# PCB_3U_ADC.net
KiCad netlist of a schematic drawn in Altium Designer
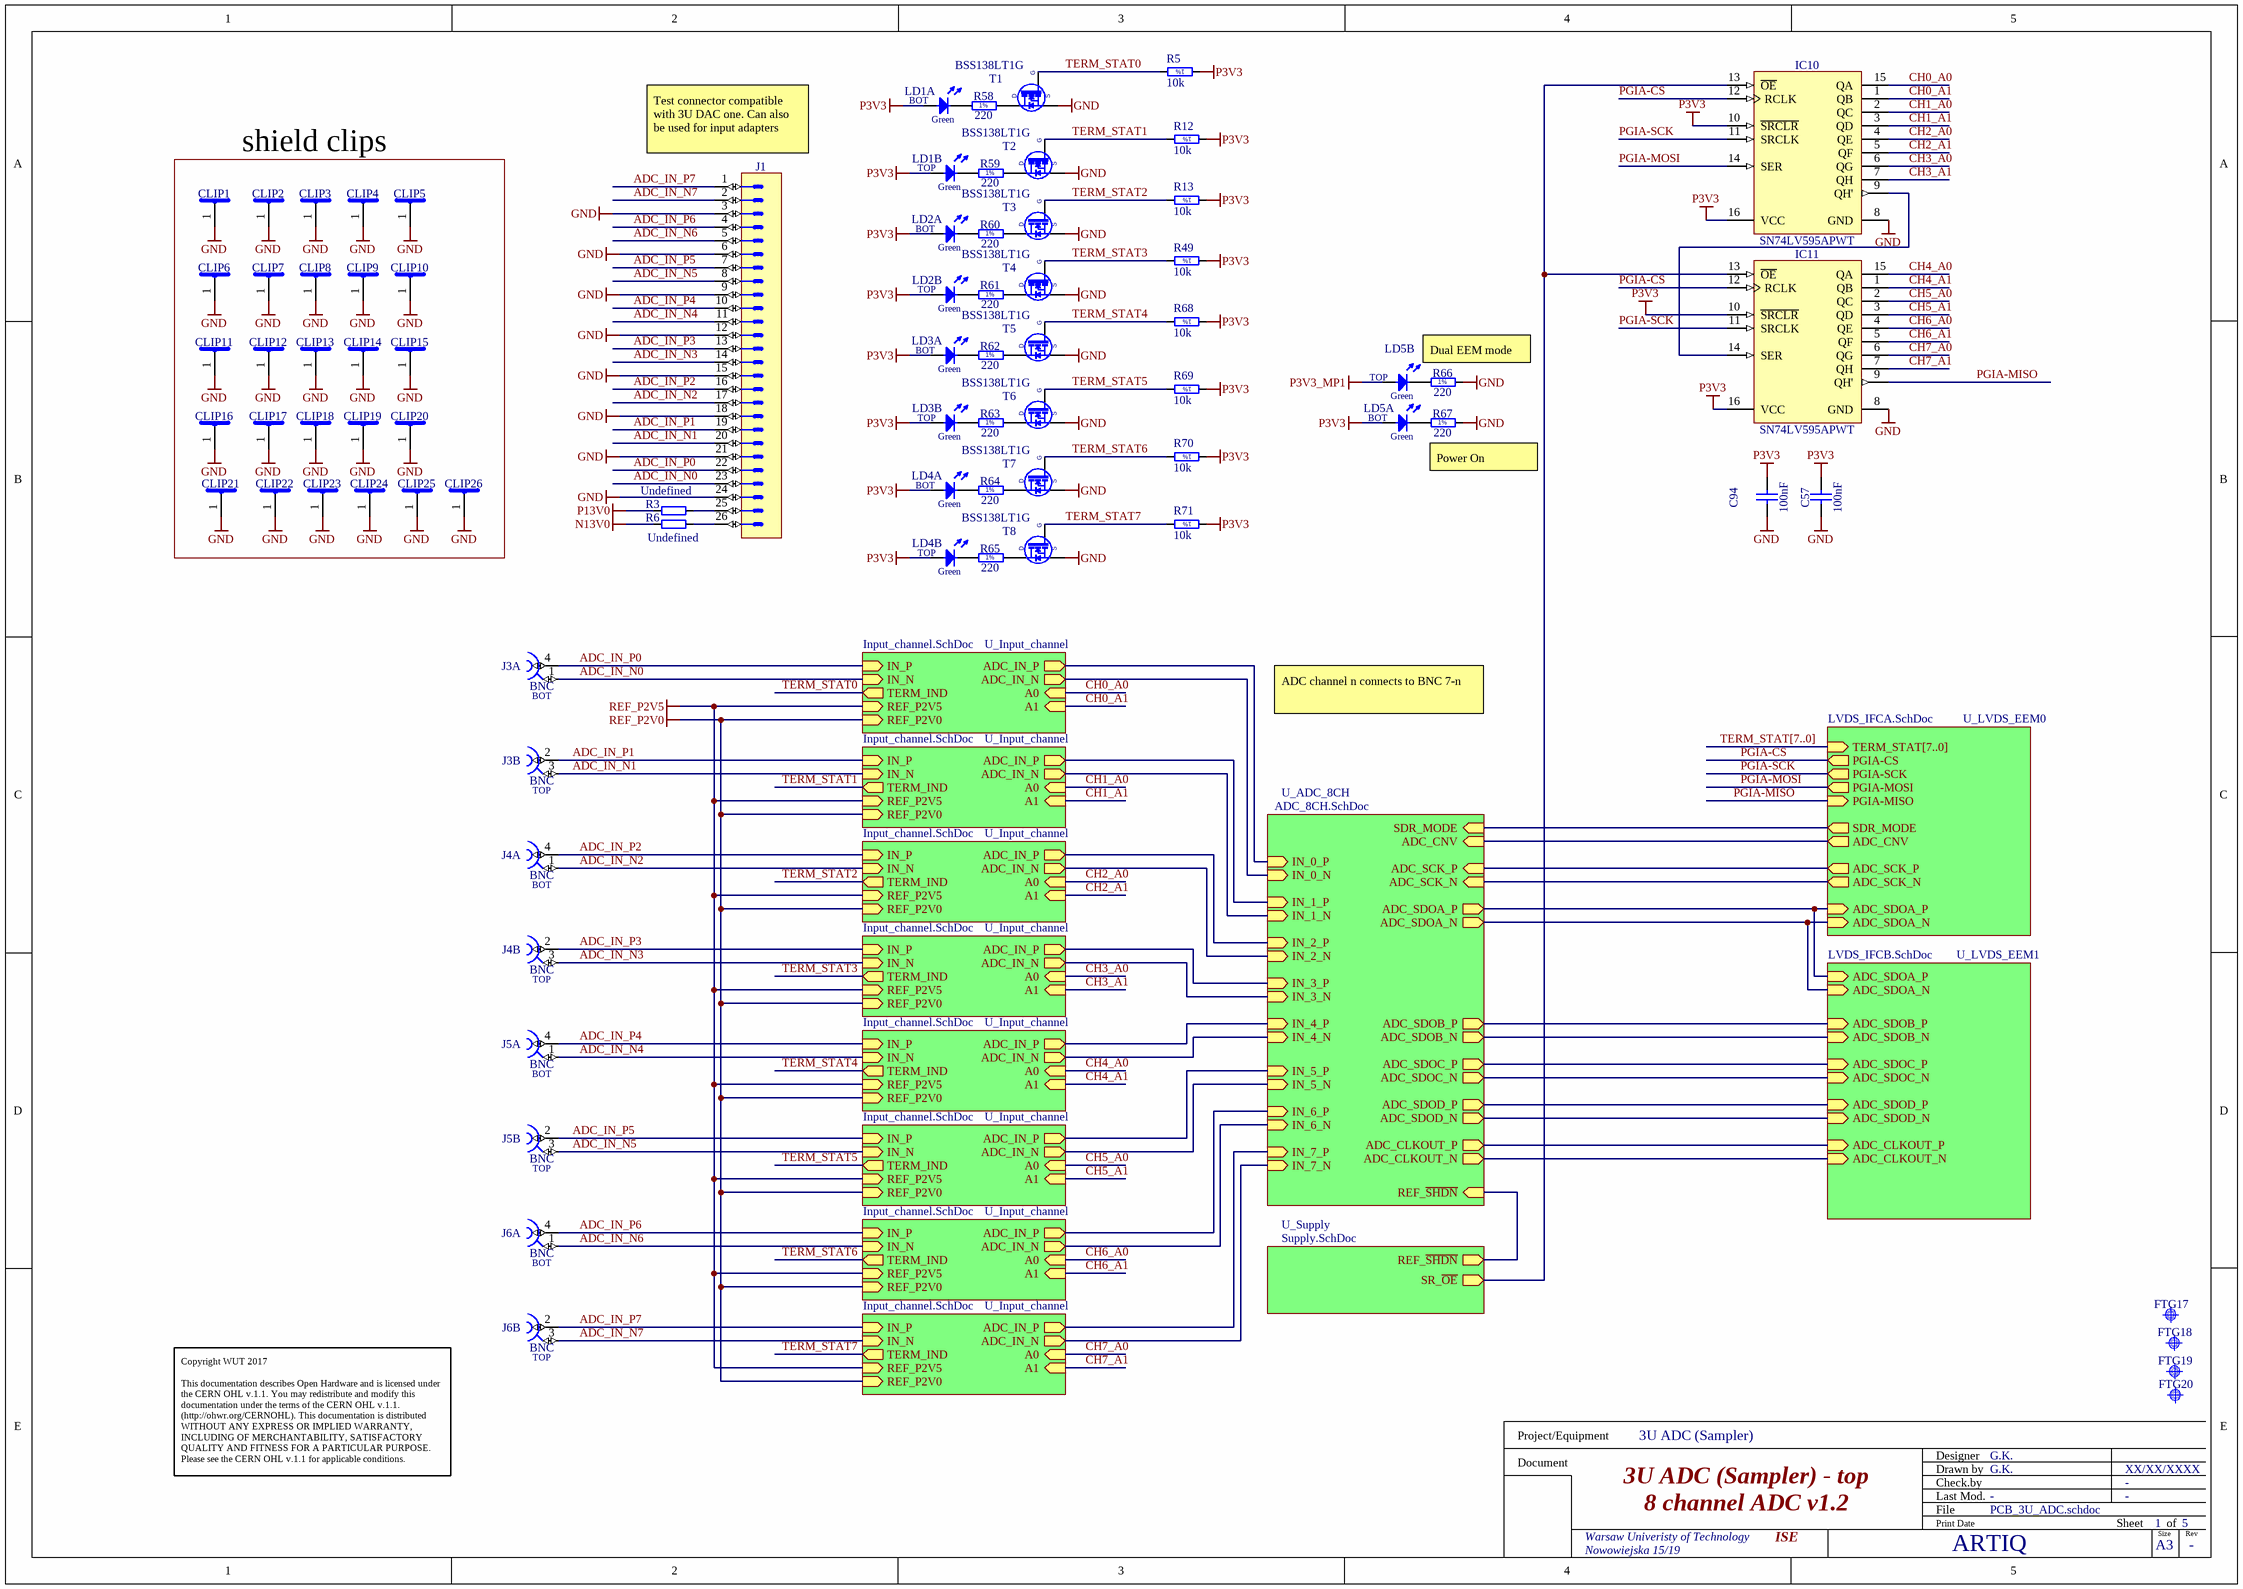
[diagram p0: PCB_3U_ADC.schdoc]

(export (version "E")
  (design (tool "Eeschema 10.0.6"))
  (components
    (comp (ref "C57")
      (value "100nF")
      (footprint "CAPC1608X87N")
      (description "Non-polarised capacitor")
      (fields
        (field (name "PART NUMBER") "CC0603_100NF_50V_10%_X7R")
        (field (name "VOLTAGE") "50V")
        (field (name "AUTHOR") "CERN DEM JLC")
      )
      (libsource (lib "Capacitors") (part "Capacitor - non polarized"))
    )
    (comp (ref "C94")
      (value "100nF")
      (footprint "CAPC1608X87N")
      (description "Non-polarised capacitor")
      (fields
        (field (name "PART NUMBER") "CC0603_100NF_50V_10%_X7R")
        (field (name "VOLTAGE") "50V")
        (field (name "AUTHOR") "CERN DEM JLC")
      )
      (libsource (lib "Capacitors") (part "Capacitor - non polarized"))
    )
    (comp (ref "CLIP1")
      (value "S1411-46R")
      (footprint "CLIP_HOLLAND-SHIELDING_LC")
      (description "Surface Mount Clip for PCB Screening Covers")
      (fields (field (name "MANUFACTURER") "HARWIN") (field (name "AUTHOR") "CERN DEM JLC"))
      (libsource (lib "LIBRARY_SCH") (part "SHIELD_CLIP"))
    )
    (comp (ref "CLIP2")
      (value "S1411-46R")
      (footprint "CLIP_HOLLAND-SHIELDING_LC")
      (description "Surface Mount Clip for PCB Screening Covers")
      (fields (field (name "MANUFACTURER") "HARWIN") (field (name "AUTHOR") "CERN DEM JLC"))
      (libsource (lib "LIBRARY_SCH") (part "SHIELD_CLIP"))
    )
    (comp (ref "CLIP3")
      (value "S1411-46R")
      (footprint "CLIP_HOLLAND-SHIELDING_LC")
      (description "Surface Mount Clip for PCB Screening Covers")
      (fields (field (name "MANUFACTURER") "HARWIN") (field (name "AUTHOR") "CERN DEM JLC"))
      (libsource (lib "LIBRARY_SCH") (part "SHIELD_CLIP"))
    )
    (comp (ref "CLIP4")
      (value "S1411-46R")
      (footprint "CLIP_HOLLAND-SHIELDING_LC")
      (description "Surface Mount Clip for PCB Screening Covers")
      (fields (field (name "MANUFACTURER") "HARWIN") (field (name "AUTHOR") "CERN DEM JLC"))
      (libsource (lib "LIBRARY_SCH") (part "SHIELD_CLIP"))
    )
    (comp (ref "CLIP5")
      (value "S1411-46R")
      (footprint "CLIP_HOLLAND-SHIELDING_LC")
      (description "Surface Mount Clip for PCB Screening Covers")
      (fields (field (name "MANUFACTURER") "HARWIN") (field (name "AUTHOR") "CERN DEM JLC"))
      (libsource (lib "LIBRARY_SCH") (part "SHIELD_CLIP"))
    )
    (comp (ref "CLIP6")
      (value "S1411-46R")
      (footprint "CLIP_HOLLAND-SHIELDING_LC")
      (description "Surface Mount Clip for PCB Screening Covers")
      (fields (field (name "MANUFACTURER") "HARWIN") (field (name "AUTHOR") "CERN DEM JLC"))
      (libsource (lib "LIBRARY_SCH") (part "SHIELD_CLIP"))
    )
    (comp (ref "CLIP7")
      (value "S1411-46R")
      (footprint "CLIP_HOLLAND-SHIELDING_LC")
      (description "Surface Mount Clip for PCB Screening Covers")
      (fields (field (name "MANUFACTURER") "HARWIN") (field (name "AUTHOR") "CERN DEM JLC"))
      (libsource (lib "LIBRARY_SCH") (part "SHIELD_CLIP"))
    )
    (comp (ref "CLIP8")
      (value "S1411-46R")
      (footprint "CLIP_HOLLAND-SHIELDING_LC")
      (description "Surface Mount Clip for PCB Screening Covers")
      (fields (field (name "MANUFACTURER") "HARWIN") (field (name "AUTHOR") "CERN DEM JLC"))
      (libsource (lib "LIBRARY_SCH") (part "SHIELD_CLIP"))
    )
    (comp (ref "CLIP9")
      (value "S1411-46R")
      (footprint "CLIP_HOLLAND-SHIELDING_LC")
      (description "Surface Mount Clip for PCB Screening Covers")
      (fields (field (name "MANUFACTURER") "HARWIN") (field (name "AUTHOR") "CERN DEM JLC"))
      (libsource (lib "LIBRARY_SCH") (part "SHIELD_CLIP"))
    )
    (comp (ref "CLIP10")
      (value "S1411-46R")
      (footprint "CLIP_HOLLAND-SHIELDING_LC")
      (description "Surface Mount Clip for PCB Screening Covers")
      (fields (field (name "MANUFACTURER") "HARWIN") (field (name "AUTHOR") "CERN DEM JLC"))
      (libsource (lib "LIBRARY_SCH") (part "SHIELD_CLIP"))
    )
    (comp (ref "CLIP11")
      (value "S1411-46R")
      (footprint "CLIP_HOLLAND-SHIELDING_LC")
      (description "Surface Mount Clip for PCB Screening Covers")
      (fields (field (name "MANUFACTURER") "HARWIN") (field (name "AUTHOR") "CERN DEM JLC"))
      (libsource (lib "LIBRARY_SCH") (part "SHIELD_CLIP"))
    )
    (comp (ref "CLIP12")
      (value "S1411-46R")
      (footprint "CLIP_HOLLAND-SHIELDING_LC")
      (description "Surface Mount Clip for PCB Screening Covers")
      (fields (field (name "MANUFACTURER") "HARWIN") (field (name "AUTHOR") "CERN DEM JLC"))
      (libsource (lib "LIBRARY_SCH") (part "SHIELD_CLIP"))
    )
    (comp (ref "CLIP13")
      (value "S1411-46R")
      (footprint "CLIP_HOLLAND-SHIELDING_LC")
      (description "Surface Mount Clip for PCB Screening Covers")
      (fields (field (name "MANUFACTURER") "HARWIN") (field (name "AUTHOR") "CERN DEM JLC"))
      (libsource (lib "LIBRARY_SCH") (part "SHIELD_CLIP"))
    )
    (comp (ref "CLIP14")
      (value "S1411-46R")
      (footprint "CLIP_HOLLAND-SHIELDING_LC")
      (description "Surface Mount Clip for PCB Screening Covers")
      (fields (field (name "MANUFACTURER") "HARWIN") (field (name "AUTHOR") "CERN DEM JLC"))
      (libsource (lib "LIBRARY_SCH") (part "SHIELD_CLIP"))
    )
    (comp (ref "CLIP15")
      (value "S1411-46R")
      (footprint "CLIP_HOLLAND-SHIELDING_LC")
      (description "Surface Mount Clip for PCB Screening Covers")
      (fields (field (name "MANUFACTURER") "HARWIN") (field (name "AUTHOR") "CERN DEM JLC"))
      (libsource (lib "LIBRARY_SCH") (part "SHIELD_CLIP"))
    )
    (comp (ref "CLIP16")
      (value "S1411-46R")
      (footprint "CLIP_HOLLAND-SHIELDING_LC")
      (description "Surface Mount Clip for PCB Screening Covers")
      (fields (field (name "MANUFACTURER") "HARWIN") (field (name "AUTHOR") "CERN DEM JLC"))
      (libsource (lib "LIBRARY_SCH") (part "SHIELD_CLIP"))
    )
    (comp (ref "CLIP17")
      (value "S1411-46R")
      (footprint "CLIP_HOLLAND-SHIELDING_LC")
      (description "Surface Mount Clip for PCB Screening Covers")
      (fields (field (name "MANUFACTURER") "HARWIN") (field (name "AUTHOR") "CERN DEM JLC"))
      (libsource (lib "LIBRARY_SCH") (part "SHIELD_CLIP"))
    )
    (comp (ref "CLIP18")
      (value "S1411-46R")
      (footprint "CLIP_HOLLAND-SHIELDING_LC")
      (description "Surface Mount Clip for PCB Screening Covers")
      (fields (field (name "MANUFACTURER") "HARWIN") (field (name "AUTHOR") "CERN DEM JLC"))
      (libsource (lib "LIBRARY_SCH") (part "SHIELD_CLIP"))
    )
    (comp (ref "CLIP19")
      (value "S1411-46R")
      (footprint "CLIP_HOLLAND-SHIELDING_LC")
      (description "Surface Mount Clip for PCB Screening Covers")
      (fields (field (name "MANUFACTURER") "HARWIN") (field (name "AUTHOR") "CERN DEM JLC"))
      (libsource (lib "LIBRARY_SCH") (part "SHIELD_CLIP"))
    )
    (comp (ref "CLIP20")
      (value "S1411-46R")
      (footprint "CLIP_HOLLAND-SHIELDING_LC")
      (description "Surface Mount Clip for PCB Screening Covers")
      (fields (field (name "MANUFACTURER") "HARWIN") (field (name "AUTHOR") "CERN DEM JLC"))
      (libsource (lib "LIBRARY_SCH") (part "SHIELD_CLIP"))
    )
    (comp (ref "CLIP21")
      (value "S1411-46R")
      (footprint "CLIP_HOLLAND-SHIELDING_LC")
      (description "Surface Mount Clip for PCB Screening Covers")
      (fields (field (name "MANUFACTURER") "HARWIN") (field (name "AUTHOR") "CERN DEM JLC"))
      (libsource (lib "LIBRARY_SCH") (part "SHIELD_CLIP"))
    )
    (comp (ref "CLIP22")
      (value "S1411-46R")
      (footprint "CLIP_HOLLAND-SHIELDING_LC")
      (description "Surface Mount Clip for PCB Screening Covers")
      (fields (field (name "MANUFACTURER") "HARWIN") (field (name "AUTHOR") "CERN DEM JLC"))
      (libsource (lib "LIBRARY_SCH") (part "SHIELD_CLIP"))
    )
    (comp (ref "CLIP23")
      (value "S1411-46R")
      (footprint "CLIP_HOLLAND-SHIELDING_LC")
      (description "Surface Mount Clip for PCB Screening Covers")
      (fields (field (name "MANUFACTURER") "HARWIN") (field (name "AUTHOR") "CERN DEM JLC"))
      (libsource (lib "LIBRARY_SCH") (part "SHIELD_CLIP"))
    )
    (comp (ref "CLIP24")
      (value "S1411-46R")
      (footprint "CLIP_HOLLAND-SHIELDING_LC")
      (description "Surface Mount Clip for PCB Screening Covers")
      (fields (field (name "MANUFACTURER") "HARWIN") (field (name "AUTHOR") "CERN DEM JLC"))
      (libsource (lib "LIBRARY_SCH") (part "SHIELD_CLIP"))
    )
    (comp (ref "CLIP25")
      (value "S1411-46R")
      (footprint "CLIP_HOLLAND-SHIELDING_LC")
      (description "Surface Mount Clip for PCB Screening Covers")
      (fields (field (name "MANUFACTURER") "HARWIN") (field (name "AUTHOR") "CERN DEM JLC"))
      (libsource (lib "LIBRARY_SCH") (part "SHIELD_CLIP"))
    )
    (comp (ref "CLIP26")
      (value "S1411-46R")
      (footprint "CLIP_HOLLAND-SHIELDING_LC")
      (description "Surface Mount Clip for PCB Screening Covers")
      (fields (field (name "MANUFACTURER") "HARWIN") (field (name "AUTHOR") "CERN DEM JLC"))
      (libsource (lib "LIBRARY_SCH") (part "SHIELD_CLIP"))
    )
    (comp (ref "FTG17")
      (value "Use only in PCB")
      (footprint "FIDUCIAL_TOP_C100-200")
      (description "Fiducial Target")
      (fields (field (name "PART NUMBER") "FIDUCIAL_TARGET_C100-200") (field (name "AUTHOR") "CERN DEM JLC"))
      (libsource (lib "Eletro-mechanical") (part "Fiducial Target"))
    )
    (comp (ref "FTG18")
      (value "Use only in PCB")
      (footprint "FIDUCIAL_TOP_S100-200")
      (description "Fiducial Target")
      (fields (field (name "PART NUMBER") "FIDUCIAL_TARGET_S100-200") (field (name "AUTHOR") "CERN DEM JLC"))
      (libsource (lib "Eletro-mechanical") (part "Fiducial Target"))
    )
    (comp (ref "FTG19")
      (value "Use only in PCB")
      (footprint "FIDUCIAL_TOP_S200-400")
      (description "Fiducial Target")
      (fields (field (name "PART NUMBER") "FIDUCIAL_TARGET_S200-400") (field (name "AUTHOR") "CERN DEM JLC"))
      (libsource (lib "Eletro-mechanical") (part "Fiducial Target"))
    )
    (comp (ref "FTG20")
      (value "Use only in PCB")
      (footprint "FIDUCIAL_TOP_S100-200")
      (description "Fiducial Target")
      (fields (field (name "PART NUMBER") "FIDUCIAL_TARGET_S100-200") (field (name "AUTHOR") "CERN DEM JLC"))
      (libsource (lib "Eletro-mechanical") (part "Fiducial Target"))
    )
    (comp (ref "IC10")
      (value "SN74LV595APWT")
      (footprint "SOP65P640X120-16N")
      (description "8-Bit Shift Register With 3-State Output Register")
      (fields (field (name "MANUFACTURER") "TEXAS INSTRUMENTS") (field (name "AUTHOR") "CERN DEM JLC"))
      (libsource (lib "ICs And Semiconductors") (part "74595"))
    )
    (comp (ref "IC11")
      (value "SN74LV595APWT")
      (footprint "SOP65P640X120-16N")
      (description "8-Bit Shift Register With 3-State Output Register")
      (fields (field (name "MANUFACTURER") "TEXAS INSTRUMENTS") (field (name "AUTHOR") "CERN DEM JLC"))
      (libsource (lib "ICs And Semiconductors") (part "74595"))
    )
    (comp (ref "J1")
      (value "Header 26")
      (footprint "3M_N2526-6002RB")
      (description "Connector 26 Male")
      (fields
        (field (name "PART NUMBER") "3M_N2526-6002RB")
        (field (name "MANUFACTURER") "3M")
        (field (name "AUTHOR") "CERN DEM JLC")
      )
      (libsource (lib "Connectors") (part "Connector 26 Male"))
    )
    (comp (ref "J3")
      (value "BNC")
      (footprint "RENHOTEC_RHT-610-0049")
      (description "Dual Right Angle 50 Ohm BNC Jack, White Valox Case")
      (fields
        (field (name "PART NUMBER") "RENHOTEC_RHT-610-0049")
        (field (name "MANUFACTURER") "RENHOTEC")
        (field (name "AUTHOR") "GK")
      )
      (libsource (lib "LIBRARY_SCH") (part "CON_BNC_DUAL"))
    )
    (comp (ref "J4")
      (value "BNC")
      (footprint "RENHOTEC_RHT-610-0049")
      (description "Dual Right Angle 50 Ohm BNC Jack, White Valox Case")
      (fields
        (field (name "PART NUMBER") "RENHOTEC_RHT-610-0049")
        (field (name "MANUFACTURER") "RENHOTEC")
        (field (name "AUTHOR") "GK")
      )
      (libsource (lib "LIBRARY_SCH") (part "CON_BNC_DUAL"))
    )
    (comp (ref "J5")
      (value "BNC")
      (footprint "RENHOTEC_RHT-610-0049")
      (description "Dual Right Angle 50 Ohm BNC Jack, White Valox Case")
      (fields
        (field (name "PART NUMBER") "RENHOTEC_RHT-610-0049")
        (field (name "MANUFACTURER") "RENHOTEC")
        (field (name "AUTHOR") "GK")
      )
      (libsource (lib "LIBRARY_SCH") (part "CON_BNC_DUAL"))
    )
    (comp (ref "J6")
      (value "BNC")
      (footprint "RENHOTEC_RHT-610-0049")
      (description "Dual Right Angle 50 Ohm BNC Jack, White Valox Case")
      (fields
        (field (name "PART NUMBER") "RENHOTEC_RHT-610-0049")
        (field (name "MANUFACTURER") "RENHOTEC")
        (field (name "AUTHOR") "GK")
      )
      (libsource (lib "LIBRARY_SCH") (part "CON_BNC_DUAL"))
    )
    (comp (ref "LD1")
      (value "Green/Green")
      (footprint "LED_DIALIGHT_571-0122F")
      (description "LED x2 Green 1C2A-BOT_3C4A-TOP")
      (fields
        (field (name "PART NUMBER") "LED_DIALIGHT_571-0122F")
        (field (name "MANUFACTURER") "DIALIGHT")
        (field (name "AUTHOR") "CERN DEM JLC")
      )
      (libsource (lib "ICs And Semiconductors") (part "LED x2 Green 1C2A-BOT_3C4A-TOP"))
    )
    (comp (ref "LD2")
      (value "Green/Green")
      (footprint "LED_DIALIGHT_571-0122F")
      (description "LED x2 Green 1C2A-BOT_3C4A-TOP")
      (fields
        (field (name "PART NUMBER") "LED_DIALIGHT_571-0122F")
        (field (name "MANUFACTURER") "DIALIGHT")
        (field (name "AUTHOR") "CERN DEM JLC")
      )
      (libsource (lib "ICs And Semiconductors") (part "LED x2 Green 1C2A-BOT_3C4A-TOP"))
    )
    (comp (ref "LD3")
      (value "Green/Green")
      (footprint "LED_DIALIGHT_571-0122F")
      (description "LED x2 Green 1C2A-BOT_3C4A-TOP")
      (fields
        (field (name "PART NUMBER") "LED_DIALIGHT_571-0122F")
        (field (name "MANUFACTURER") "DIALIGHT")
        (field (name "AUTHOR") "CERN DEM JLC")
      )
      (libsource (lib "ICs And Semiconductors") (part "LED x2 Green 1C2A-BOT_3C4A-TOP"))
    )
    (comp (ref "LD4")
      (value "Green/Green")
      (footprint "LED_DIALIGHT_571-0122F")
      (description "LED x2 Green 1C2A-BOT_3C4A-TOP")
      (fields
        (field (name "PART NUMBER") "LED_DIALIGHT_571-0122F")
        (field (name "MANUFACTURER") "DIALIGHT")
        (field (name "AUTHOR") "CERN DEM JLC")
      )
      (libsource (lib "ICs And Semiconductors") (part "LED x2 Green 1C2A-BOT_3C4A-TOP"))
    )
    (comp (ref "LD5")
      (value "Green/Green")
      (footprint "LED_DIALIGHT_571-0122F")
      (description "LED x2 Green 1C2A-BOT_3C4A-TOP")
      (fields
        (field (name "PART NUMBER") "LED_DIALIGHT_571-0122F")
        (field (name "MANUFACTURER") "DIALIGHT")
        (field (name "AUTHOR") "CERN DEM JLC")
      )
      (libsource (lib "ICs And Semiconductors") (part "LED x2 Green 1C2A-BOT_3C4A-TOP"))
    )
    (comp (ref "R3")
      (value "Undefined")
      (footprint "RESC1608X55N")
      (description "Resistor")
      (fields (field (name "PART NUMBER") "R0603_NO-VALUE") (field (name "AUTHOR") "CERN DEM JLC"))
      (libsource (lib "Resistors") (part "Resistor"))
    )
    (comp (ref "R5")
      (value "10k")
      (footprint "RESC1005X40N")
      (description "Resistor - 1%")
      (fields
        (field (name "PART NUMBER") "R0402_10K_1%_0.0625W_100PPM")
        (field (name "POWER") "0.0625W")
        (field (name "AUTHOR") "CERN DEM JLC")
      )
      (libsource (lib "Resistors") (part "Resistor - 1%"))
    )
    (comp (ref "R6")
      (value "Undefined")
      (footprint "RESC1608X55N")
      (description "Resistor")
      (fields (field (name "PART NUMBER") "R0603_NO-VALUE") (field (name "AUTHOR") "CERN DEM JLC"))
      (libsource (lib "Resistors") (part "Resistor"))
    )
    (comp (ref "R12")
      (value "10k")
      (footprint "RESC1005X40N")
      (description "Resistor - 1%")
      (fields
        (field (name "PART NUMBER") "R0402_10K_1%_0.0625W_100PPM")
        (field (name "POWER") "0.0625W")
        (field (name "AUTHOR") "CERN DEM JLC")
      )
      (libsource (lib "Resistors") (part "Resistor - 1%"))
    )
    (comp (ref "R13")
      (value "10k")
      (footprint "RESC1005X40N")
      (description "Resistor - 1%")
      (fields
        (field (name "PART NUMBER") "R0402_10K_1%_0.0625W_100PPM")
        (field (name "POWER") "0.0625W")
        (field (name "AUTHOR") "CERN DEM JLC")
      )
      (libsource (lib "Resistors") (part "Resistor - 1%"))
    )
    (comp (ref "R49")
      (value "10k")
      (footprint "RESC1005X40N")
      (description "Resistor - 1%")
      (fields
        (field (name "PART NUMBER") "R0402_10K_1%_0.0625W_100PPM")
        (field (name "POWER") "0.0625W")
        (field (name "AUTHOR") "CERN DEM JLC")
      )
      (libsource (lib "Resistors") (part "Resistor - 1%"))
    )
    (comp (ref "R58")
      (value "220")
      (footprint "RESC1608X55N")
      (description "Resistor - 1%")
      (fields
        (field (name "PART NUMBER") "R0603_220R_1%_0.1W_100PPM")
        (field (name "POWER") "0.1W")
        (field (name "AUTHOR") "CERN DEM JLC")
      )
      (libsource (lib "Resistors") (part "Resistor - 1%"))
    )
    (comp (ref "R59")
      (value "220")
      (footprint "RESC1608X55N")
      (description "Resistor - 1%")
      (fields
        (field (name "PART NUMBER") "R0603_220R_1%_0.1W_100PPM")
        (field (name "POWER") "0.1W")
        (field (name "AUTHOR") "CERN DEM JLC")
      )
      (libsource (lib "Resistors") (part "Resistor - 1%"))
    )
    (comp (ref "R60")
      (value "220")
      (footprint "RESC1608X55N")
      (description "Resistor - 1%")
      (fields
        (field (name "PART NUMBER") "R0603_220R_1%_0.1W_100PPM")
        (field (name "POWER") "0.1W")
        (field (name "AUTHOR") "CERN DEM JLC")
      )
      (libsource (lib "Resistors") (part "Resistor - 1%"))
    )
    (comp (ref "R61")
      (value "220")
      (footprint "RESC1608X55N")
      (description "Resistor - 1%")
      (fields
        (field (name "PART NUMBER") "R0603_220R_1%_0.1W_100PPM")
        (field (name "POWER") "0.1W")
        (field (name "AUTHOR") "CERN DEM JLC")
      )
      (libsource (lib "Resistors") (part "Resistor - 1%"))
    )
    (comp (ref "R62")
      (value "220")
      (footprint "RESC1608X55N")
      (description "Resistor - 1%")
      (fields
        (field (name "PART NUMBER") "R0603_220R_1%_0.1W_100PPM")
        (field (name "POWER") "0.1W")
        (field (name "AUTHOR") "CERN DEM JLC")
      )
      (libsource (lib "Resistors") (part "Resistor - 1%"))
    )
    (comp (ref "R63")
      (value "220")
      (footprint "RESC1608X55N")
      (description "Resistor - 1%")
      (fields
        (field (name "PART NUMBER") "R0603_220R_1%_0.1W_100PPM")
        (field (name "POWER") "0.1W")
        (field (name "AUTHOR") "CERN DEM JLC")
      )
      (libsource (lib "Resistors") (part "Resistor - 1%"))
    )
    (comp (ref "R64")
      (value "220")
      (footprint "RESC1608X55N")
      (description "Resistor - 1%")
      (fields
        (field (name "PART NUMBER") "R0603_220R_1%_0.1W_100PPM")
        (field (name "POWER") "0.1W")
        (field (name "AUTHOR") "CERN DEM JLC")
      )
      (libsource (lib "Resistors") (part "Resistor - 1%"))
    )
    (comp (ref "R65")
      (value "220")
      (footprint "RESC1608X55N")
      (description "Resistor - 1%")
      (fields
        (field (name "PART NUMBER") "R0603_220R_1%_0.1W_100PPM")
        (field (name "POWER") "0.1W")
        (field (name "AUTHOR") "CERN DEM JLC")
      )
      (libsource (lib "Resistors") (part "Resistor - 1%"))
    )
    (comp (ref "R66")
      (value "220")
      (footprint "RESC1608X55N")
      (description "Resistor - 1%")
      (fields
        (field (name "PART NUMBER") "R0603_220R_1%_0.1W_100PPM")
        (field (name "POWER") "0.1W")
        (field (name "AUTHOR") "CERN DEM JLC")
      )
      (libsource (lib "Resistors") (part "Resistor - 1%"))
    )
    (comp (ref "R67")
      (value "220")
      (footprint "RESC1608X55N")
      (description "Resistor - 1%")
      (fields
        (field (name "PART NUMBER") "R0603_220R_1%_0.1W_100PPM")
        (field (name "POWER") "0.1W")
        (field (name "AUTHOR") "CERN DEM JLC")
      )
      (libsource (lib "Resistors") (part "Resistor - 1%"))
    )
    (comp (ref "R68")
      (value "10k")
      (footprint "RESC1005X40N")
      (description "Resistor - 1%")
      (fields
        (field (name "PART NUMBER") "R0402_10K_1%_0.0625W_100PPM")
        (field (name "POWER") "0.0625W")
        (field (name "AUTHOR") "CERN DEM JLC")
      )
      (libsource (lib "Resistors") (part "Resistor - 1%"))
    )
    (comp (ref "R69")
      (value "10k")
      (footprint "RESC1005X40N")
      (description "Resistor - 1%")
      (fields
        (field (name "PART NUMBER") "R0402_10K_1%_0.0625W_100PPM")
        (field (name "POWER") "0.0625W")
        (field (name "AUTHOR") "CERN DEM JLC")
      )
      (libsource (lib "Resistors") (part "Resistor - 1%"))
    )
    (comp (ref "R70")
      (value "10k")
      (footprint "RESC1005X40N")
      (description "Resistor - 1%")
      (fields
        (field (name "PART NUMBER") "R0402_10K_1%_0.0625W_100PPM")
        (field (name "POWER") "0.0625W")
        (field (name "AUTHOR") "CERN DEM JLC")
      )
      (libsource (lib "Resistors") (part "Resistor - 1%"))
    )
    (comp (ref "R71")
      (value "10k")
      (footprint "RESC1005X40N")
      (description "Resistor - 1%")
      (fields
        (field (name "PART NUMBER") "R0402_10K_1%_0.0625W_100PPM")
        (field (name "POWER") "0.0625W")
        (field (name "AUTHOR") "CERN DEM JLC")
      )
      (libsource (lib "Resistors") (part "Resistor - 1%"))
    )
    (comp (ref "T1")
      (value "BSS138LT1G")
      (footprint "SOT95P240X110-3N")
      (description "N-CHANNEL MOSFET WITH DIODE")
      (fields (field (name "MANUFACTURER") "ON SEMICONDUCTOR") (field (name "AUTHOR") "CERN DEM JLC"))
      (libsource (lib "ICs And Semiconductors") (part "N-MOSFET-D 1G 2S 3D"))
    )
    (comp (ref "T2")
      (value "BSS138LT1G")
      (footprint "SOT95P240X110-3N")
      (description "N-CHANNEL MOSFET WITH DIODE")
      (fields (field (name "MANUFACTURER") "ON SEMICONDUCTOR") (field (name "AUTHOR") "CERN DEM JLC"))
      (libsource (lib "ICs And Semiconductors") (part "N-MOSFET-D 1G 2S 3D"))
    )
    (comp (ref "T3")
      (value "BSS138LT1G")
      (footprint "SOT95P240X110-3N")
      (description "N-CHANNEL MOSFET WITH DIODE")
      (fields (field (name "MANUFACTURER") "ON SEMICONDUCTOR") (field (name "AUTHOR") "CERN DEM JLC"))
      (libsource (lib "ICs And Semiconductors") (part "N-MOSFET-D 1G 2S 3D"))
    )
    (comp (ref "T4")
      (value "BSS138LT1G")
      (footprint "SOT95P240X110-3N")
      (description "N-CHANNEL MOSFET WITH DIODE")
      (fields (field (name "MANUFACTURER") "ON SEMICONDUCTOR") (field (name "AUTHOR") "CERN DEM JLC"))
      (libsource (lib "ICs And Semiconductors") (part "N-MOSFET-D 1G 2S 3D"))
    )
    (comp (ref "T5")
      (value "BSS138LT1G")
      (footprint "SOT95P240X110-3N")
      (description "N-CHANNEL MOSFET WITH DIODE")
      (fields (field (name "MANUFACTURER") "ON SEMICONDUCTOR") (field (name "AUTHOR") "CERN DEM JLC"))
      (libsource (lib "ICs And Semiconductors") (part "N-MOSFET-D 1G 2S 3D"))
    )
    (comp (ref "T6")
      (value "BSS138LT1G")
      (footprint "SOT95P240X110-3N")
      (description "N-CHANNEL MOSFET WITH DIODE")
      (fields (field (name "MANUFACTURER") "ON SEMICONDUCTOR") (field (name "AUTHOR") "CERN DEM JLC"))
      (libsource (lib "ICs And Semiconductors") (part "N-MOSFET-D 1G 2S 3D"))
    )
    (comp (ref "T7")
      (value "BSS138LT1G")
      (footprint "SOT95P240X110-3N")
      (description "N-CHANNEL MOSFET WITH DIODE")
      (fields (field (name "MANUFACTURER") "ON SEMICONDUCTOR") (field (name "AUTHOR") "CERN DEM JLC"))
      (libsource (lib "ICs And Semiconductors") (part "N-MOSFET-D 1G 2S 3D"))
    )
    (comp (ref "T8")
      (value "BSS138LT1G")
      (footprint "SOT95P240X110-3N")
      (description "N-CHANNEL MOSFET WITH DIODE")
      (fields (field (name "MANUFACTURER") "ON SEMICONDUCTOR") (field (name "AUTHOR") "CERN DEM JLC"))
      (libsource (lib "ICs And Semiconductors") (part "N-MOSFET-D 1G 2S 3D"))
    )
  )
  (nets
    (net (code "5") (name "/ADC_IN_N0") (class "Default")
      (node (ref "J1") (pin "23") (pinfunction "23_23") (pintype "bidirectional"))
      (node (ref "J3") (pin "1") (pinfunction "1_1") (pintype "bidirectional"))
    )
    (net (code "6") (name "/ADC_IN_N1") (class "Default")
      (node (ref "J1") (pin "20") (pinfunction "20_20") (pintype "bidirectional"))
      (node (ref "J3") (pin "3") (pinfunction "3_3") (pintype "bidirectional"))
    )
    (net (code "7") (name "/ADC_IN_N2") (class "Default")
      (node (ref "J1") (pin "17") (pinfunction "17_17") (pintype "bidirectional"))
      (node (ref "J4") (pin "1") (pinfunction "1_1") (pintype "bidirectional"))
    )
    (net (code "8") (name "/ADC_IN_N3") (class "Default")
      (node (ref "J1") (pin "14") (pinfunction "14_14") (pintype "bidirectional"))
      (node (ref "J4") (pin "3") (pinfunction "3_3") (pintype "bidirectional"))
    )
    (net (code "9") (name "/ADC_IN_N4") (class "Default")
      (node (ref "J1") (pin "11") (pinfunction "11_11") (pintype "bidirectional"))
      (node (ref "J5") (pin "1") (pinfunction "1_1") (pintype "bidirectional"))
    )
    (net (code "10") (name "/ADC_IN_N5") (class "Default")
      (node (ref "J1") (pin "8") (pinfunction "8_8") (pintype "bidirectional"))
      (node (ref "J5") (pin "3") (pinfunction "3_3") (pintype "bidirectional"))
    )
    (net (code "11") (name "/ADC_IN_N6") (class "Default")
      (node (ref "J1") (pin "5") (pinfunction "5_5") (pintype "bidirectional"))
      (node (ref "J6") (pin "1") (pinfunction "1_1") (pintype "bidirectional"))
    )
    (net (code "12") (name "/ADC_IN_N7") (class "Default")
      (node (ref "J1") (pin "2") (pinfunction "2_2") (pintype "bidirectional"))
      (node (ref "J6") (pin "3") (pinfunction "3_3") (pintype "bidirectional"))
    )
    (net (code "21") (name "/ADC_IN_P0") (class "Default")
      (node (ref "J1") (pin "22") (pinfunction "22_22") (pintype "bidirectional"))
      (node (ref "J3") (pin "4") (pinfunction "4_4") (pintype "bidirectional"))
    )
    (net (code "22") (name "/ADC_IN_P1") (class "Default")
      (node (ref "J1") (pin "19") (pinfunction "19_19") (pintype "bidirectional"))
      (node (ref "J3") (pin "2") (pinfunction "2_2") (pintype "bidirectional"))
    )
    (net (code "23") (name "/ADC_IN_P2") (class "Default")
      (node (ref "J1") (pin "16") (pinfunction "16_16") (pintype "bidirectional"))
      (node (ref "J4") (pin "4") (pinfunction "4_4") (pintype "bidirectional"))
    )
    (net (code "24") (name "/ADC_IN_P3") (class "Default")
      (node (ref "J1") (pin "13") (pinfunction "13_13") (pintype "bidirectional"))
      (node (ref "J4") (pin "2") (pinfunction "2_2") (pintype "bidirectional"))
    )
    (net (code "25") (name "/ADC_IN_P4") (class "Default")
      (node (ref "J1") (pin "10") (pinfunction "10_10") (pintype "bidirectional"))
      (node (ref "J5") (pin "4") (pinfunction "4_4") (pintype "bidirectional"))
    )
    (net (code "26") (name "/ADC_IN_P5") (class "Default")
      (node (ref "J1") (pin "7") (pinfunction "7_7") (pintype "bidirectional"))
      (node (ref "J5") (pin "2") (pinfunction "2_2") (pintype "bidirectional"))
    )
    (net (code "27") (name "/ADC_IN_P6") (class "Default")
      (node (ref "J1") (pin "4") (pinfunction "4_4") (pintype "bidirectional"))
      (node (ref "J6") (pin "4") (pinfunction "4_4") (pintype "bidirectional"))
    )
    (net (code "28") (name "/ADC_IN_P7") (class "Default")
      (node (ref "J1") (pin "1") (pinfunction "1_1") (pintype "bidirectional"))
      (node (ref "J6") (pin "2") (pinfunction "2_2") (pintype "bidirectional"))
    )
    (net (code "46") (name "/CH0_A0") (class "Default")
      (node (ref "IC10") (pin "15") (pinfunction "QA_15") (pintype "tri_state"))
    )
    (net (code "47") (name "/CH0_A1") (class "Default")
      (node (ref "IC10") (pin "1") (pinfunction "QB_1") (pintype "tri_state"))
    )
    (net (code "48") (name "/CH1_A0") (class "Default")
      (node (ref "IC10") (pin "2") (pinfunction "QC_2") (pintype "tri_state"))
    )
    (net (code "49") (name "/CH1_A1") (class "Default")
      (node (ref "IC10") (pin "3") (pinfunction "QD_3") (pintype "tri_state"))
    )
    (net (code "50") (name "/CH2_A0") (class "Default")
      (node (ref "IC10") (pin "4") (pinfunction "QE_4") (pintype "tri_state"))
    )
    (net (code "51") (name "/CH2_A1") (class "Default")
      (node (ref "IC10") (pin "5") (pinfunction "QF_5") (pintype "tri_state"))
    )
    (net (code "52") (name "/CH3_A0") (class "Default")
      (node (ref "IC10") (pin "6") (pinfunction "QG_6") (pintype "tri_state"))
    )
    (net (code "53") (name "/CH3_A1") (class "Default")
      (node (ref "IC10") (pin "7") (pinfunction "QH_7") (pintype "tri_state"))
    )
    (net (code "54") (name "/CH4_A0") (class "Default")
      (node (ref "IC11") (pin "15") (pinfunction "QA_15") (pintype "tri_state"))
    )
    (net (code "55") (name "/CH4_A1") (class "Default")
      (node (ref "IC11") (pin "1") (pinfunction "QB_1") (pintype "tri_state"))
    )
    (net (code "56") (name "/CH5_A0") (class "Default")
      (node (ref "IC11") (pin "2") (pinfunction "QC_2") (pintype "tri_state"))
    )
    (net (code "57") (name "/CH5_A1") (class "Default")
      (node (ref "IC11") (pin "3") (pinfunction "QD_3") (pintype "tri_state"))
    )
    (net (code "58") (name "/CH6_A0") (class "Default")
      (node (ref "IC11") (pin "4") (pinfunction "QE_4") (pintype "tri_state"))
    )
    (net (code "59") (name "/CH6_A1") (class "Default")
      (node (ref "IC11") (pin "5") (pinfunction "QF_5") (pintype "tri_state"))
    )
    (net (code "60") (name "/CH7_A0") (class "Default")
      (node (ref "IC11") (pin "6") (pinfunction "QG_6") (pintype "tri_state"))
    )
    (net (code "61") (name "/CH7_A1") (class "Default")
      (node (ref "IC11") (pin "7") (pinfunction "QH_7") (pintype "tri_state"))
    )
    (net (code "62") (name "/PGIA-CS") (class "Default")
      (node (ref "IC10") (pin "12") (pinfunction "RCLK_12") (pintype "input"))
      (node (ref "IC11") (pin "12") (pinfunction "RCLK_12") (pintype "input"))
    )
    (net (code "63") (name "/PGIA-MISO") (class "Default")
      (node (ref "IC11") (pin "9") (pinfunction "QH'_9") (pintype "output"))
    )
    (net (code "64") (name "/PGIA-MOSI") (class "Default")
      (node (ref "IC10") (pin "14") (pinfunction "SER_14") (pintype "input"))
    )
    (net (code "65") (name "/PGIA-SCK") (class "Default")
      (node (ref "IC10") (pin "11") (pinfunction "SRCLK_11") (pintype "input"))
      (node (ref "IC11") (pin "11") (pinfunction "SRCLK_11") (pintype "input"))
    )
    (net (code "68") (name "/SR_~{OE}") (class "Default")
      (node (ref "IC10") (pin "13") (pinfunction "~{OE}_13") (pintype "input"))
      (node (ref "IC11") (pin "13") (pinfunction "~{OE}_13") (pintype "input"))
    )
    (net (code "69") (name "/TERM_STAT0") (class "Default")
      (node (ref "R5") (pin "2") (pinfunction "2_2") (pintype "passive"))
      (node (ref "T1") (pin "1") (pinfunction "G_1") (pintype "passive"))
    )
    (net (code "70") (name "/TERM_STAT1") (class "Default")
      (node (ref "R12") (pin "2") (pinfunction "2_2") (pintype "passive"))
      (node (ref "T2") (pin "1") (pinfunction "G_1") (pintype "passive"))
    )
    (net (code "71") (name "/TERM_STAT2") (class "Default")
      (node (ref "R13") (pin "2") (pinfunction "2_2") (pintype "passive"))
      (node (ref "T3") (pin "1") (pinfunction "G_1") (pintype "passive"))
    )
    (net (code "72") (name "/TERM_STAT3") (class "Default")
      (node (ref "R49") (pin "2") (pinfunction "2_2") (pintype "passive"))
      (node (ref "T4") (pin "1") (pinfunction "G_1") (pintype "passive"))
    )
    (net (code "73") (name "/TERM_STAT4") (class "Default")
      (node (ref "R68") (pin "2") (pinfunction "2_2") (pintype "passive"))
      (node (ref "T5") (pin "1") (pinfunction "G_1") (pintype "passive"))
    )
    (net (code "74") (name "/TERM_STAT5") (class "Default")
      (node (ref "R69") (pin "2") (pinfunction "2_2") (pintype "passive"))
      (node (ref "T6") (pin "1") (pinfunction "G_1") (pintype "passive"))
    )
    (net (code "75") (name "/TERM_STAT6") (class "Default")
      (node (ref "R70") (pin "2") (pinfunction "2_2") (pintype "passive"))
      (node (ref "T7") (pin "1") (pinfunction "G_1") (pintype "passive"))
    )
    (net (code "76") (name "/TERM_STAT7") (class "Default")
      (node (ref "R71") (pin "2") (pinfunction "2_2") (pintype "passive"))
      (node (ref "T8") (pin "1") (pinfunction "G_1") (pintype "passive"))
    )
    (net (code "78") (name "GND") (class "Default")
      (node (ref "C57") (pin "1") (pinfunction "1_1") (pintype "passive"))
      (node (ref "C94") (pin "1") (pinfunction "1_1") (pintype "passive"))
      (node (ref "CLIP1") (pin "1") (pinfunction "1_1") (pintype "passive"))
      (node (ref "CLIP10") (pin "1") (pinfunction "1_1") (pintype "passive"))
      (node (ref "CLIP11") (pin "1") (pinfunction "1_1") (pintype "passive"))
      (node (ref "CLIP12") (pin "1") (pinfunction "1_1") (pintype "passive"))
      (node (ref "CLIP13") (pin "1") (pinfunction "1_1") (pintype "passive"))
      (node (ref "CLIP14") (pin "1") (pinfunction "1_1") (pintype "passive"))
      (node (ref "CLIP15") (pin "1") (pinfunction "1_1") (pintype "passive"))
      (node (ref "CLIP16") (pin "1") (pinfunction "1_1") (pintype "passive"))
      (node (ref "CLIP17") (pin "1") (pinfunction "1_1") (pintype "passive"))
      (node (ref "CLIP18") (pin "1") (pinfunction "1_1") (pintype "passive"))
      (node (ref "CLIP19") (pin "1") (pinfunction "1_1") (pintype "passive"))
      (node (ref "CLIP2") (pin "1") (pinfunction "1_1") (pintype "passive"))
      (node (ref "CLIP20") (pin "1") (pinfunction "1_1") (pintype "passive"))
      (node (ref "CLIP21") (pin "1") (pinfunction "1_1") (pintype "passive"))
      (node (ref "CLIP22") (pin "1") (pinfunction "1_1") (pintype "passive"))
      (node (ref "CLIP23") (pin "1") (pinfunction "1_1") (pintype "passive"))
      (node (ref "CLIP24") (pin "1") (pinfunction "1_1") (pintype "passive"))
      (node (ref "CLIP25") (pin "1") (pinfunction "1_1") (pintype "passive"))
      (node (ref "CLIP26") (pin "1") (pinfunction "1_1") (pintype "passive"))
      (node (ref "CLIP3") (pin "1") (pinfunction "1_1") (pintype "passive"))
      (node (ref "CLIP4") (pin "1") (pinfunction "1_1") (pintype "passive"))
      (node (ref "CLIP5") (pin "1") (pinfunction "1_1") (pintype "passive"))
      (node (ref "CLIP6") (pin "1") (pinfunction "1_1") (pintype "passive"))
      (node (ref "CLIP7") (pin "1") (pinfunction "1_1") (pintype "passive"))
      (node (ref "CLIP8") (pin "1") (pinfunction "1_1") (pintype "passive"))
      (node (ref "CLIP9") (pin "1") (pinfunction "1_1") (pintype "passive"))
      (node (ref "IC10") (pin "8") (pinfunction "GND_8") (pintype "power_in"))
      (node (ref "IC11") (pin "8") (pinfunction "GND_8") (pintype "power_in"))
      (node (ref "J1") (pin "12") (pinfunction "12_12") (pintype "bidirectional"))
      (node (ref "J1") (pin "15") (pinfunction "15_15") (pintype "bidirectional"))
      (node (ref "J1") (pin "18") (pinfunction "18_18") (pintype "bidirectional"))
      (node (ref "J1") (pin "21") (pinfunction "21_21") (pintype "bidirectional"))
      (node (ref "J1") (pin "24") (pinfunction "24_24") (pintype "bidirectional"))
      (node (ref "J1") (pin "3") (pinfunction "3_3") (pintype "bidirectional"))
      (node (ref "J1") (pin "6") (pinfunction "6_6") (pintype "bidirectional"))
      (node (ref "J1") (pin "9") (pinfunction "9_9") (pintype "bidirectional"))
      (node (ref "R66") (pin "2") (pinfunction "2_2") (pintype "passive"))
      (node (ref "R67") (pin "2") (pinfunction "2_2") (pintype "passive"))
      (node (ref "T1") (pin "2") (pinfunction "S_2") (pintype "passive"))
      (node (ref "T2") (pin "2") (pinfunction "S_2") (pintype "passive"))
      (node (ref "T3") (pin "2") (pinfunction "S_2") (pintype "passive"))
      (node (ref "T4") (pin "2") (pinfunction "S_2") (pintype "passive"))
      (node (ref "T5") (pin "2") (pinfunction "S_2") (pintype "passive"))
      (node (ref "T6") (pin "2") (pinfunction "S_2") (pintype "passive"))
      (node (ref "T7") (pin "2") (pinfunction "S_2") (pintype "passive"))
      (node (ref "T8") (pin "2") (pinfunction "S_2") (pintype "passive"))
    )
    (net (code "79") (name "N13V0") (class "Default")
      (node (ref "R6") (pin "2") (pinfunction "2_2") (pintype "passive"))
    )
    (net (code "80") (name "Net-(IC10-QH')") (class "Default")
      (node (ref "IC10") (pin "9") (pinfunction "QH'_9") (pintype "output"))
      (node (ref "IC11") (pin "14") (pinfunction "SER_14") (pintype "input"))
    )
    (net (code "81") (name "Net-(J1-Pad25)") (class "Default")
      (node (ref "J1") (pin "25") (pinfunction "25_25") (pintype "bidirectional"))
      (node (ref "R3") (pin "1") (pinfunction "1_1") (pintype "passive"))
    )
    (net (code "82") (name "Net-(J1-Pad26)") (class "Default")
      (node (ref "J1") (pin "26") (pinfunction "26_26") (pintype "bidirectional"))
      (node (ref "R6") (pin "1") (pinfunction "1_1") (pintype "passive"))
    )
    (net (code "83") (name "Net-(LD1A-C)") (class "Default")
      (node (ref "LD1") (pin "1") (pinfunction "C_1") (pintype "passive"))
      (node (ref "R58") (pin "1") (pinfunction "1_1") (pintype "passive"))
    )
    (net (code "84") (name "Net-(LD1B-C)") (class "Default")
      (node (ref "LD1") (pin "3") (pinfunction "C_3") (pintype "passive"))
      (node (ref "R59") (pin "1") (pinfunction "1_1") (pintype "passive"))
    )
    (net (code "85") (name "Net-(LD2A-C)") (class "Default")
      (node (ref "LD2") (pin "1") (pinfunction "C_1") (pintype "passive"))
      (node (ref "R60") (pin "1") (pinfunction "1_1") (pintype "passive"))
    )
    (net (code "86") (name "Net-(LD2B-C)") (class "Default")
      (node (ref "LD2") (pin "3") (pinfunction "C_3") (pintype "passive"))
      (node (ref "R61") (pin "1") (pinfunction "1_1") (pintype "passive"))
    )
    (net (code "87") (name "Net-(LD3A-C)") (class "Default")
      (node (ref "LD3") (pin "1") (pinfunction "C_1") (pintype "passive"))
      (node (ref "R62") (pin "1") (pinfunction "1_1") (pintype "passive"))
    )
    (net (code "88") (name "Net-(LD3B-C)") (class "Default")
      (node (ref "LD3") (pin "3") (pinfunction "C_3") (pintype "passive"))
      (node (ref "R63") (pin "1") (pinfunction "1_1") (pintype "passive"))
    )
    (net (code "89") (name "Net-(LD4A-C)") (class "Default")
      (node (ref "LD4") (pin "1") (pinfunction "C_1") (pintype "passive"))
      (node (ref "R64") (pin "1") (pinfunction "1_1") (pintype "passive"))
    )
    (net (code "90") (name "Net-(LD4B-C)") (class "Default")
      (node (ref "LD4") (pin "3") (pinfunction "C_3") (pintype "passive"))
      (node (ref "R65") (pin "1") (pinfunction "1_1") (pintype "passive"))
    )
    (net (code "91") (name "Net-(LD5A-C)") (class "Default")
      (node (ref "LD5") (pin "1") (pinfunction "C_1") (pintype "passive"))
      (node (ref "R67") (pin "1") (pinfunction "1_1") (pintype "passive"))
    )
    (net (code "92") (name "Net-(LD5B-C)") (class "Default")
      (node (ref "LD5") (pin "3") (pinfunction "C_3") (pintype "passive"))
      (node (ref "R66") (pin "1") (pinfunction "1_1") (pintype "passive"))
    )
    (net (code "93") (name "Net-(T1-D)") (class "Default")
      (node (ref "R58") (pin "2") (pinfunction "2_2") (pintype "passive"))
      (node (ref "T1") (pin "3") (pinfunction "D_3") (pintype "passive"))
    )
    (net (code "94") (name "Net-(T2-D)") (class "Default")
      (node (ref "R59") (pin "2") (pinfunction "2_2") (pintype "passive"))
      (node (ref "T2") (pin "3") (pinfunction "D_3") (pintype "passive"))
    )
    (net (code "95") (name "Net-(T3-D)") (class "Default")
      (node (ref "R60") (pin "2") (pinfunction "2_2") (pintype "passive"))
      (node (ref "T3") (pin "3") (pinfunction "D_3") (pintype "passive"))
    )
    (net (code "96") (name "Net-(T4-D)") (class "Default")
      (node (ref "R61") (pin "2") (pinfunction "2_2") (pintype "passive"))
      (node (ref "T4") (pin "3") (pinfunction "D_3") (pintype "passive"))
    )
    (net (code "97") (name "Net-(T5-D)") (class "Default")
      (node (ref "R62") (pin "2") (pinfunction "2_2") (pintype "passive"))
      (node (ref "T5") (pin "3") (pinfunction "D_3") (pintype "passive"))
    )
    (net (code "98") (name "Net-(T6-D)") (class "Default")
      (node (ref "R63") (pin "2") (pinfunction "2_2") (pintype "passive"))
      (node (ref "T6") (pin "3") (pinfunction "D_3") (pintype "passive"))
    )
    (net (code "99") (name "Net-(T7-D)") (class "Default")
      (node (ref "R64") (pin "2") (pinfunction "2_2") (pintype "passive"))
      (node (ref "T7") (pin "3") (pinfunction "D_3") (pintype "passive"))
    )
    (net (code "100") (name "Net-(T8-D)") (class "Default")
      (node (ref "R65") (pin "2") (pinfunction "2_2") (pintype "passive"))
      (node (ref "T8") (pin "3") (pinfunction "D_3") (pintype "passive"))
    )
    (net (code "101") (name "P3V3") (class "Default")
      (node (ref "C57") (pin "2") (pinfunction "2_2") (pintype "passive"))
      (node (ref "C94") (pin "2") (pinfunction "2_2") (pintype "passive"))
      (node (ref "IC10") (pin "10") (pinfunction "~{SRCLR}_10") (pintype "input"))
      (node (ref "IC10") (pin "16") (pinfunction "VCC_16") (pintype "power_in"))
      (node (ref "IC11") (pin "10") (pinfunction "~{SRCLR}_10") (pintype "input"))
      (node (ref "IC11") (pin "16") (pinfunction "VCC_16") (pintype "power_in"))
      (node (ref "LD1") (pin "2") (pinfunction "A_2") (pintype "passive"))
      (node (ref "LD1") (pin "4") (pinfunction "A_4") (pintype "passive"))
      (node (ref "LD2") (pin "2") (pinfunction "A_2") (pintype "passive"))
      (node (ref "LD2") (pin "4") (pinfunction "A_4") (pintype "passive"))
      (node (ref "LD3") (pin "2") (pinfunction "A_2") (pintype "passive"))
      (node (ref "LD3") (pin "4") (pinfunction "A_4") (pintype "passive"))
      (node (ref "LD4") (pin "2") (pinfunction "A_2") (pintype "passive"))
      (node (ref "LD4") (pin "4") (pinfunction "A_4") (pintype "passive"))
      (node (ref "LD5") (pin "2") (pinfunction "A_2") (pintype "passive"))
      (node (ref "R12") (pin "1") (pinfunction "1_1") (pintype "passive"))
      (node (ref "R13") (pin "1") (pinfunction "1_1") (pintype "passive"))
      (node (ref "R49") (pin "1") (pinfunction "1_1") (pintype "passive"))
      (node (ref "R5") (pin "1") (pinfunction "1_1") (pintype "passive"))
      (node (ref "R68") (pin "1") (pinfunction "1_1") (pintype "passive"))
      (node (ref "R69") (pin "1") (pinfunction "1_1") (pintype "passive"))
      (node (ref "R70") (pin "1") (pinfunction "1_1") (pintype "passive"))
      (node (ref "R71") (pin "1") (pinfunction "1_1") (pintype "passive"))
    )
    (net (code "102") (name "P3V3_MP1") (class "Default")
      (node (ref "LD5") (pin "4") (pinfunction "A_4") (pintype "passive"))
    )
    (net (code "103") (name "P13V0") (class "Default")
      (node (ref "R3") (pin "2") (pinfunction "2_2") (pintype "passive"))
    )
  )
)
